# schematic.net
KiCad netlist of a schematic drawn in Altium Designer
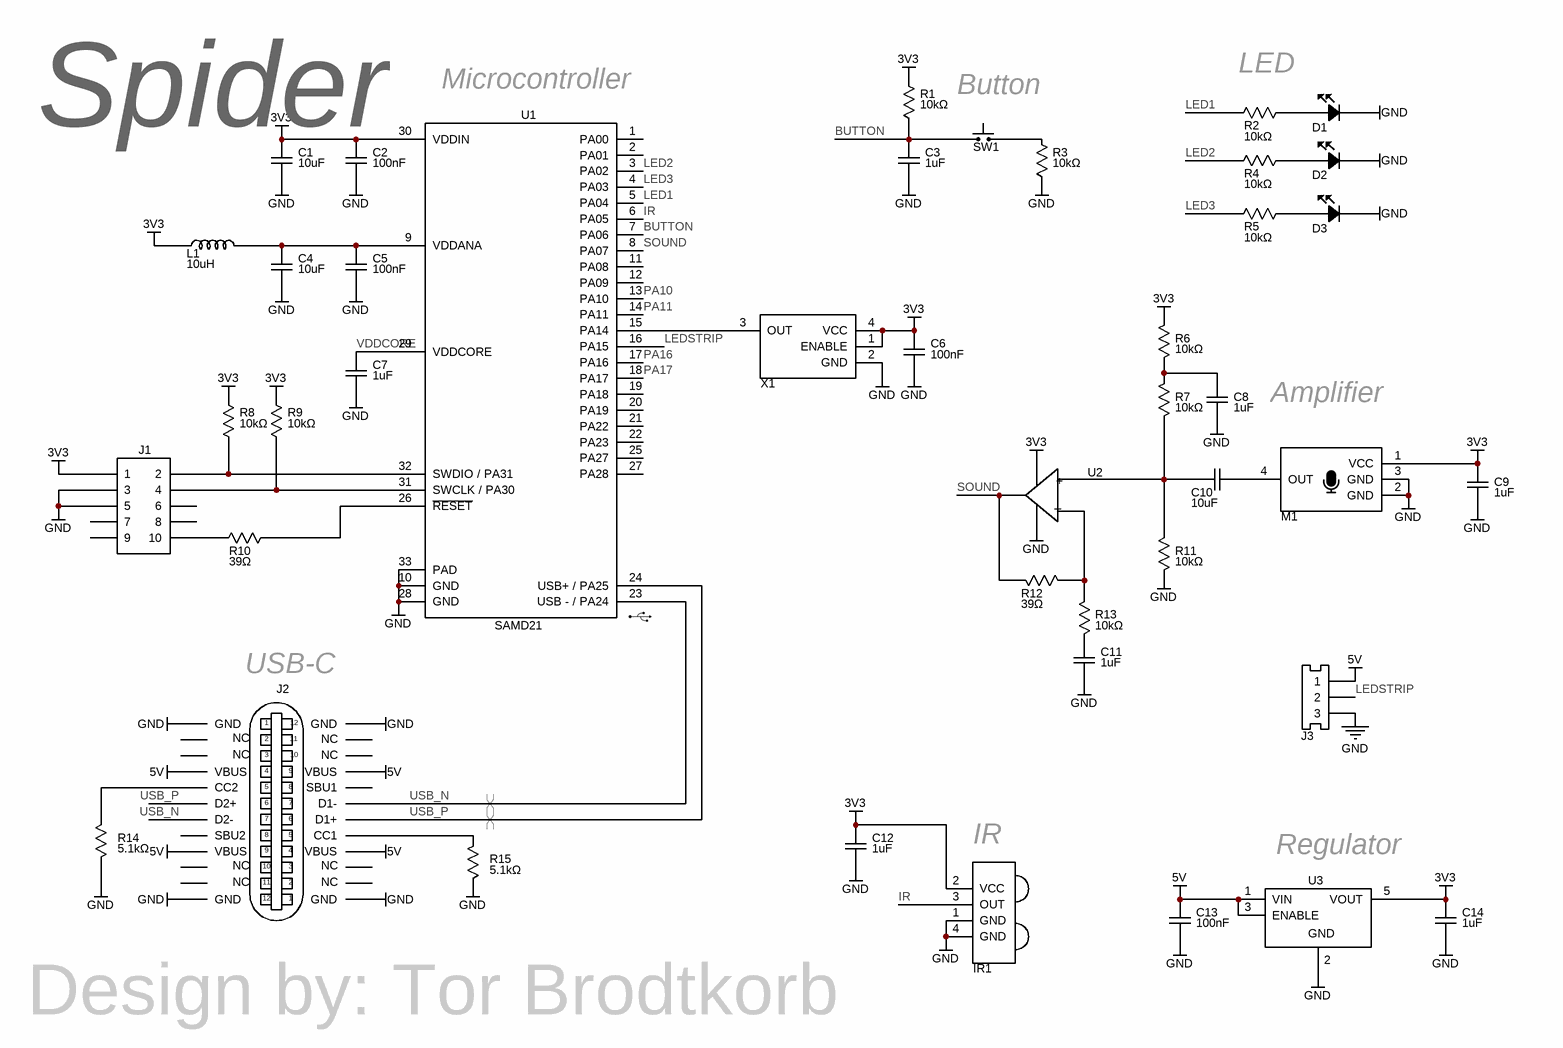
[diagram p0: schematic.SchDoc]

(export (version "E")
  (design (tool "Eeschema 10.0.6"))
  (components
    (comp (ref "C1")
      (value "10uF")
      (footprint "capacitor 0603")
      (description "Capacitor 0603")
      (fields (field (name "Comment") "passive_5"))
      (libsource (lib "passive") (part "passive_5"))
    )
    (comp (ref "C2")
      (value "100nF")
      (footprint "capacitor 0603")
      (description "Capacitor 0603")
      (fields (field (name "Comment") "passive_5"))
      (libsource (lib "passive") (part "passive_5"))
    )
    (comp (ref "C3")
      (value "1uF")
      (footprint "capacitor 0603")
      (description "Capacitor 0603")
      (fields (field (name "Comment") "passive_5"))
      (libsource (lib "passive") (part "passive_5"))
    )
    (comp (ref "C4")
      (value "10uF")
      (footprint "capacitor 0603")
      (description "Capacitor 0603")
      (fields (field (name "Comment") "passive_5"))
      (libsource (lib "passive") (part "passive_5"))
    )
    (comp (ref "C5")
      (value "100nF")
      (footprint "capacitor 0603")
      (description "Capacitor 0603")
      (fields (field (name "Comment") "passive_5"))
      (libsource (lib "passive") (part "passive_5"))
    )
    (comp (ref "C6")
      (value "100nF")
      (footprint "capacitor 0603")
      (description "Capacitor 0603")
      (fields (field (name "Comment") "passive_5"))
      (libsource (lib "passive") (part "passive_5"))
    )
    (comp (ref "C7")
      (value "1uF")
      (footprint "capacitor 0603")
      (description "Capacitor 0603")
      (fields (field (name "Comment") "passive_5"))
      (libsource (lib "passive") (part "passive_5"))
    )
    (comp (ref "C8")
      (value "1uF")
      (footprint "capacitor 0603")
      (description "Capacitor 0603")
      (fields (field (name "Comment") "passive_5"))
      (libsource (lib "passive") (part "passive_5"))
    )
    (comp (ref "C9")
      (value "1uF")
      (footprint "capacitor 0603")
      (description "Capacitor 0603")
      (fields (field (name "Comment") "passive_5"))
      (libsource (lib "passive") (part "passive_5"))
    )
    (comp (ref "C10")
      (value "10uF")
      (footprint "capacitor 0603")
      (description "Capacitor 0603")
      (fields (field (name "Comment") "passive_5"))
      (libsource (lib "passive") (part "passive_5"))
    )
    (comp (ref "C11")
      (value "1uF")
      (footprint "capacitor 0603")
      (description "Capacitor 0603")
      (fields (field (name "Comment") "passive_5"))
      (libsource (lib "passive") (part "passive_5"))
    )
    (comp (ref "C12")
      (value "1uF")
      (footprint "capacitor 0603")
      (description "Capacitor 0603")
      (fields (field (name "Comment") "passive_5"))
      (libsource (lib "passive") (part "passive_5"))
    )
    (comp (ref "C13")
      (value "100nF")
      (footprint "capacitor 0603")
      (description "Capacitor 0603")
      (fields (field (name "Comment") "passive_5"))
      (libsource (lib "passive") (part "passive_5"))
    )
    (comp (ref "C14")
      (value "1uF")
      (footprint "capacitor 0603")
      (description "Capacitor 0603")
      (fields (field (name "Comment") "passive_5"))
      (libsource (lib "passive") (part "passive_5"))
    )
    (comp (ref "D1")
      (value "LED White")
      (footprint "LED 0603 white")
      (description "LED 0603 white")
      (libsource (lib "diode") (part "diode_6"))
    )
    (comp (ref "D2")
      (value "LED White")
      (footprint "LED 0603 white")
      (description "LED 0603 white")
      (libsource (lib "diode") (part "diode_6"))
    )
    (comp (ref "D3")
      (value "LED White")
      (footprint "LED 0603 white")
      (description "LED 0603 white")
      (libsource (lib "diode") (part "diode_6"))
    )
    (comp (ref "IR1")
      (value "sensor_1")
      (footprint "TSSP77038TR")
      (description "IR receiver, 38 kHz, 40m, SMD")
      (libsource (lib "sensor") (part "sensor_1"))
    )
    (comp (ref "J1")
      (value "Header 1.27mm")
      (footprint "header male 2x5, pitch 1.27mm")
      (description "Header male 2x5, pitch 1.27mm")
      (libsource (lib "connector") (part "connector_17"))
    )
    (comp (ref "J2")
      (value "USB 2.0")
      (footprint "USB4105-GF-A")
      (description "USB-C (2.0)")
      (libsource (lib "connector") (part "connector_35"))
    )
    (comp (ref "J3")
      (value "connector_41")
      (footprint "S3B-XH-A (LF)(SN)")
      (description "JST connector 1x3, pitch 2.5mm, right angle, TH")
      (libsource (lib "connector") (part "connector_41"))
    )
    (comp (ref "L1")
      (value "10uH")
      (footprint "inductor 0603")
      (description "Inductor 0603")
      (fields (field (name "Comment") "passive_9"))
      (libsource (lib "passive") (part "passive_9"))
    )
    (comp (ref "M1")
      (value "sensor_2")
      (footprint "SPU0410HR5H-PB")
      (description "Microphone, MEMS, 100 Hz - 10 kHz, 3.3V,  SMD")
      (libsource (lib "sensor") (part "sensor_2"))
    )
    (comp (ref "R1")
      (value "10kΩ")
      (footprint "resistor 0603")
      (description "Resistor 0603")
      (fields (field (name "Comment") "passive_2"))
      (libsource (lib "passive") (part "passive_2"))
    )
    (comp (ref "R2")
      (value "10kΩ")
      (footprint "resistor 0603")
      (description "Resistor 0603")
      (fields (field (name "Comment") "passive_2"))
      (libsource (lib "passive") (part "passive_2"))
    )
    (comp (ref "R3")
      (value "10kΩ")
      (footprint "resistor 0603")
      (description "Resistor 0603")
      (fields (field (name "Comment") "passive_2"))
      (libsource (lib "passive") (part "passive_2"))
    )
    (comp (ref "R4")
      (value "10kΩ")
      (footprint "resistor 0603")
      (description "Resistor 0603")
      (fields (field (name "Comment") "passive_2"))
      (libsource (lib "passive") (part "passive_2"))
    )
    (comp (ref "R5")
      (value "10kΩ")
      (footprint "resistor 0603")
      (description "Resistor 0603")
      (fields (field (name "Comment") "passive_2"))
      (libsource (lib "passive") (part "passive_2"))
    )
    (comp (ref "R6")
      (value "10kΩ")
      (footprint "resistor 0603")
      (description "Resistor 0603")
      (fields (field (name "Comment") "passive_2"))
      (libsource (lib "passive") (part "passive_2"))
    )
    (comp (ref "R7")
      (value "10kΩ")
      (footprint "resistor 0603")
      (description "Resistor 0603")
      (fields (field (name "Comment") "passive_2"))
      (libsource (lib "passive") (part "passive_2"))
    )
    (comp (ref "R8")
      (value "10kΩ")
      (footprint "resistor 0603")
      (description "Resistor 0603")
      (fields (field (name "Comment") "passive_2"))
      (libsource (lib "passive") (part "passive_2"))
    )
    (comp (ref "R9")
      (value "10kΩ")
      (footprint "resistor 0603")
      (description "Resistor 0603")
      (fields (field (name "Comment") "passive_2"))
      (libsource (lib "passive") (part "passive_2"))
    )
    (comp (ref "R10")
      (value "39Ω")
      (footprint "resistor 0603")
      (description "Resistor 0603")
      (fields (field (name "Comment") "passive_2"))
      (libsource (lib "passive") (part "passive_2"))
    )
    (comp (ref "R11")
      (value "10kΩ")
      (footprint "resistor 0603")
      (description "Resistor 0603")
      (fields (field (name "Comment") "passive_2"))
      (libsource (lib "passive") (part "passive_2"))
    )
    (comp (ref "R12")
      (value "39Ω")
      (footprint "resistor 0603")
      (description "Resistor 0603")
      (fields (field (name "Comment") "passive_2"))
      (libsource (lib "passive") (part "passive_2"))
    )
    (comp (ref "R13")
      (value "10kΩ")
      (footprint "resistor 0603")
      (description "Resistor 0603")
      (fields (field (name "Comment") "passive_2"))
      (libsource (lib "passive") (part "passive_2"))
    )
    (comp (ref "R14")
      (value "5.1kΩ")
      (footprint "resistor 0603")
      (description "Resistor 0603")
      (fields (field (name "Comment") "passive_2"))
      (libsource (lib "passive") (part "passive_2"))
    )
    (comp (ref "R15")
      (value "5.1kΩ")
      (footprint "resistor 0603")
      (description "Resistor 0603")
      (fields (field (name "Comment") "passive_2"))
      (libsource (lib "passive") (part "passive_2"))
    )
    (comp (ref "SW1")
      (value "connector_35")
      (footprint "KMR621NG LFS")
      (description "Tactile switch SMD, tiny")
      (libsource (lib "sensor") (part "connector_35"))
    )
    (comp (ref "U1")
      (value "SAMD21")
      (footprint "ATSAMD21E17D-MUT")
      (description "SAMD21, 48 MHz, 128KB flash, 16KB RAM, 32 pins, USB device, QFN")
      (libsource (lib "cpu") (part "cpu_0"))
    )
    (comp (ref "U2")
      (value "ic_6")
      (footprint "MCP6241T-E/OT")
      (description "OpAmp, 1 circuit, rail-to-rail, single supply, 1.8V to 5V, SOT23-5")
      (libsource (lib "integrated-circuit") (part "ic_6"))
    )
    (comp (ref "U3")
      (value "regulator_1")
      (footprint "TCR2EF33,LM(CT")
      (description "LDO fixed, 3.3V output, 0.2V dropout, 200mA")
      (libsource (lib "voltage-regulator") (part "regulator_1"))
    )
    (comp (ref "X1")
      (value "8 MHz")
      (footprint "DSC6001CE2A-008.0000")
      (description "Oscillator, 8MHz, 3.3V, 3.2mm x 2.5mm")
      (libsource (lib "oscillator") (part "oscillator_2"))
    )
  )
  (nets
    (net (code "1") (name "/BUTTON") (class "Default")
      (node (ref "C3") (pin "2") (pinfunction "2_2") (pintype "passive"))
      (node (ref "R1") (pin "2") (pinfunction "2_2") (pintype "passive"))
      (node (ref "SW1") (pin "1") (pintype "passive"))
      (node (ref "U1") (pin "7") (pinfunction "PA06_7") (pintype "passive"))
    )
    (net (code "2") (name "/IR") (class "Default")
      (node (ref "IR1") (pin "3") (pinfunction "OUT_3") (pintype "passive"))
      (node (ref "U1") (pin "6") (pinfunction "PA05_6") (pintype "passive"))
    )
    (net (code "3") (name "/LED1") (class "Default")
      (node (ref "R2") (pin "2") (pinfunction "2_2") (pintype "passive"))
      (node (ref "U1") (pin "5") (pinfunction "PA04_5") (pintype "passive"))
    )
    (net (code "4") (name "/LED2") (class "Default")
      (node (ref "R4") (pin "2") (pinfunction "2_2") (pintype "passive"))
      (node (ref "U1") (pin "3") (pinfunction "PA02_3") (pintype "passive"))
    )
    (net (code "5") (name "/LED3") (class "Default")
      (node (ref "R5") (pin "2") (pinfunction "2_2") (pintype "passive"))
      (node (ref "U1") (pin "4") (pinfunction "PA03_4") (pintype "passive"))
    )
    (net (code "6") (name "/LEDSTRIP") (class "Default")
      (node (ref "J3") (pin "2") (pinfunction "2_2") (pintype "passive"))
      (node (ref "U1") (pin "16") (pinfunction "PA15_16") (pintype "passive"))
    )
    (net (code "7") (name "/PA10") (class "Default")
      (node (ref "U1") (pin "13") (pinfunction "PA10_13") (pintype "passive"))
    )
    (net (code "8") (name "/PA11") (class "Default")
      (node (ref "U1") (pin "14") (pinfunction "PA11_14") (pintype "passive"))
    )
    (net (code "9") (name "/PA16") (class "Default")
      (node (ref "U1") (pin "17") (pinfunction "PA16_17") (pintype "passive"))
    )
    (net (code "10") (name "/PA17") (class "Default")
      (node (ref "U1") (pin "18") (pinfunction "PA17_18") (pintype "passive"))
    )
    (net (code "11") (name "/SOUND") (class "Default")
      (node (ref "R12") (pin "2") (pinfunction "2_2") (pintype "passive"))
      (node (ref "U1") (pin "8") (pinfunction "PA07_8") (pintype "passive"))
      (node (ref "U2") (pin "1") (pintype "passive"))
    )
    (net (code "12") (name "/USB_N") (class "Default")
      (node (ref "J2") (pin "A7") (pinfunction "D1-_A7") (pintype "passive"))
      (node (ref "J2") (pin "B7") (pinfunction "D2-_B7") (pintype "passive"))
      (node (ref "U1") (pin "23") (pinfunction "USB_-_/_PA24_23") (pintype "passive"))
    )
    (net (code "13") (name "/USB_P") (class "Default")
      (node (ref "J2") (pin "A6") (pinfunction "D1+_A6") (pintype "passive"))
      (node (ref "J2") (pin "B6") (pinfunction "D2+_B6") (pintype "passive"))
      (node (ref "U1") (pin "24") (pinfunction "USB+_/_PA25_24") (pintype "passive"))
    )
    (net (code "14") (name "/VDDCORE") (class "Default")
      (node (ref "C7") (pin "2") (pinfunction "2_2") (pintype "passive"))
      (node (ref "U1") (pin "29") (pinfunction "VDDCORE_29") (pintype "passive"))
    )
    (net (code "15") (name "3V3") (class "Default")
      (node (ref "C1") (pin "2") (pinfunction "2_2") (pintype "passive"))
      (node (ref "C12") (pin "2") (pinfunction "2_2") (pintype "passive"))
      (node (ref "C14") (pin "2") (pinfunction "2_2") (pintype "passive"))
      (node (ref "C2") (pin "2") (pinfunction "2_2") (pintype "passive"))
      (node (ref "C6") (pin "2") (pinfunction "2_2") (pintype "passive"))
      (node (ref "C9") (pin "2") (pinfunction "2_2") (pintype "passive"))
      (node (ref "IR1") (pin "2") (pinfunction "VCC_2") (pintype "passive"))
      (node (ref "J1") (pin "1") (pinfunction "1_1") (pintype "passive"))
      (node (ref "L1") (pin "1") (pintype "passive"))
      (node (ref "M1") (pin "1") (pinfunction "VCC_1") (pintype "passive"))
      (node (ref "R1") (pin "1") (pintype "passive"))
      (node (ref "R6") (pin "2") (pinfunction "2_2") (pintype "passive"))
      (node (ref "R8") (pin "2") (pinfunction "2_2") (pintype "passive"))
      (node (ref "R9") (pin "2") (pinfunction "2_2") (pintype "passive"))
      (node (ref "U1") (pin "30") (pinfunction "VDDIN_30") (pintype "passive"))
      (node (ref "U2") (pin "5") (pintype "passive"))
      (node (ref "U3") (pin "5") (pinfunction "VOUT_5") (pintype "passive"))
      (node (ref "X1") (pin "1") (pinfunction "ENABLE_1") (pintype "passive"))
      (node (ref "X1") (pin "4") (pinfunction "VCC_4") (pintype "passive"))
    )
    (net (code "16") (name "5V") (class "Default")
      (node (ref "C13") (pin "2") (pinfunction "2_2") (pintype "passive"))
      (node (ref "J2") (pin "A4_B9") (pinfunction "VBUS_A4_B9") (pintype "passive"))
      (node (ref "J2") (pin "B4_A9") (pinfunction "VBUS_B4_A9") (pintype "passive"))
      (node (ref "J3") (pin "1") (pinfunction "1_1") (pintype "passive"))
      (node (ref "U3") (pin "1") (pinfunction "VIN_1") (pintype "passive"))
      (node (ref "U3") (pin "3") (pinfunction "ENABLE_3") (pintype "passive"))
    )
    (net (code "17") (name "GND") (class "Default")
      (node (ref "C1") (pin "1") (pinfunction "1_1") (pintype "passive"))
      (node (ref "C11") (pin "1") (pinfunction "1_1") (pintype "passive"))
      (node (ref "C12") (pin "1") (pinfunction "1_1") (pintype "passive"))
      (node (ref "C13") (pin "1") (pinfunction "1_1") (pintype "passive"))
      (node (ref "C14") (pin "1") (pinfunction "1_1") (pintype "passive"))
      (node (ref "C2") (pin "1") (pinfunction "1_1") (pintype "passive"))
      (node (ref "C3") (pin "1") (pinfunction "1_1") (pintype "passive"))
      (node (ref "C4") (pin "1") (pinfunction "1_1") (pintype "passive"))
      (node (ref "C5") (pin "1") (pinfunction "1_1") (pintype "passive"))
      (node (ref "C6") (pin "1") (pinfunction "1_1") (pintype "passive"))
      (node (ref "C7") (pin "1") (pinfunction "1_1") (pintype "passive"))
      (node (ref "C8") (pin "1") (pinfunction "1_1") (pintype "passive"))
      (node (ref "C9") (pin "1") (pinfunction "1_1") (pintype "passive"))
      (node (ref "D1") (pin "2") (pinfunction "2_2") (pintype "passive"))
      (node (ref "D2") (pin "2") (pinfunction "2_2") (pintype "passive"))
      (node (ref "D3") (pin "2") (pinfunction "2_2") (pintype "passive"))
      (node (ref "IR1") (pin "1") (pinfunction "GND_1") (pintype "passive"))
      (node (ref "IR1") (pin "4") (pinfunction "GND_4") (pintype "passive"))
      (node (ref "J1") (pin "3") (pinfunction "3_3") (pintype "passive"))
      (node (ref "J1") (pin "5") (pinfunction "5_5") (pintype "passive"))
      (node (ref "J2") (pin "A1_B12") (pinfunction "GND_A1_B12") (pintype "passive"))
      (node (ref "J2") (pin "B1_A12") (pinfunction "GND_B1_A12") (pintype "passive"))
      (node (ref "J3") (pin "3") (pinfunction "3_3") (pintype "passive"))
      (node (ref "M1") (pin "2") (pinfunction "GND_2") (pintype "passive"))
      (node (ref "M1") (pin "3") (pinfunction "GND_3") (pintype "passive"))
      (node (ref "R11") (pin "1") (pintype "passive"))
      (node (ref "R14") (pin "1") (pintype "passive"))
      (node (ref "R15") (pin "1") (pintype "passive"))
      (node (ref "R3") (pin "2") (pinfunction "2_2") (pintype "passive"))
      (node (ref "U1") (pin "10") (pinfunction "GND_10") (pintype "passive"))
      (node (ref "U1") (pin "28") (pinfunction "GND_28") (pintype "passive"))
      (node (ref "U1") (pin "33") (pinfunction "PAD_33") (pintype "passive"))
      (node (ref "U2") (pin "2") (pintype "passive"))
      (node (ref "U3") (pin "2") (pintype "passive"))
      (node (ref "X1") (pin "2") (pinfunction "GND_2") (pintype "passive"))
    )
    (net (code "18") (name "Net-(C8-Pad2)") (class "Default")
      (node (ref "C8") (pin "2") (pinfunction "2_2") (pintype "passive"))
      (node (ref "R6") (pin "1") (pintype "passive"))
      (node (ref "R7") (pin "2") (pinfunction "2_2") (pintype "passive"))
    )
    (net (code "19") (name "Net-(C10-Pad1)") (class "Default")
      (node (ref "C10") (pin "1") (pinfunction "1_1") (pintype "passive"))
      (node (ref "R11") (pin "2") (pinfunction "2_2") (pintype "passive"))
      (node (ref "R7") (pin "1") (pintype "passive"))
      (node (ref "U2") (pin "3") (pintype "passive"))
    )
    (net (code "20") (name "Net-(C11-Pad2)") (class "Default")
      (node (ref "C11") (pin "2") (pinfunction "2_2") (pintype "passive"))
      (node (ref "R13") (pin "1") (pintype "passive"))
    )
    (net (code "21") (name "Net-(D1-Pad1)") (class "Default")
      (node (ref "D1") (pin "1") (pinfunction "1_1") (pintype "passive"))
      (node (ref "R2") (pin "1") (pintype "passive"))
    )
    (net (code "22") (name "Net-(D2-Pad1)") (class "Default")
      (node (ref "D2") (pin "1") (pinfunction "1_1") (pintype "passive"))
      (node (ref "R4") (pin "1") (pintype "passive"))
    )
    (net (code "23") (name "Net-(D3-Pad1)") (class "Default")
      (node (ref "D3") (pin "1") (pinfunction "1_1") (pintype "passive"))
      (node (ref "R5") (pin "1") (pintype "passive"))
    )
    (net (code "24") (name "Net-(J1-Pad10)") (class "Default")
      (node (ref "J1") (pin "10") (pinfunction "10_10") (pintype "passive"))
      (node (ref "R10") (pin "1") (pintype "passive"))
    )
    (net (code "25") (name "Net-(J2-CC1)") (class "Default")
      (node (ref "J2") (pin "A5") (pinfunction "CC1_A5") (pintype "passive"))
      (node (ref "R15") (pin "2") (pinfunction "2_2") (pintype "passive"))
    )
    (net (code "26") (name "Net-(J2-CC2)") (class "Default")
      (node (ref "J2") (pin "B5") (pinfunction "CC2_B5") (pintype "passive"))
      (node (ref "R14") (pin "2") (pinfunction "2_2") (pintype "passive"))
    )
    (net (code "27") (name "Net-(M1-OUT)") (class "Default")
      (node (ref "C10") (pin "2") (pinfunction "2_2") (pintype "passive"))
      (node (ref "M1") (pin "4") (pinfunction "OUT_4") (pintype "passive"))
    )
    (net (code "28") (name "Net-(R3-Pad1)") (class "Default")
      (node (ref "R3") (pin "1") (pintype "passive"))
      (node (ref "SW1") (pin "2") (pintype "passive"))
    )
    (net (code "29") (name "Net-(R12-Pad1)") (class "Default")
      (node (ref "R12") (pin "1") (pintype "passive"))
      (node (ref "R13") (pin "2") (pinfunction "2_2") (pintype "passive"))
      (node (ref "U2") (pin "4") (pintype "passive"))
    )
    (net (code "30") (name "Net-(U1-PA14)") (class "Default")
      (node (ref "U1") (pin "15") (pinfunction "PA14_15") (pintype "passive"))
      (node (ref "X1") (pin "3") (pinfunction "OUT_3") (pintype "passive"))
    )
    (net (code "31") (name "Net-(U1-SWCLK_{slash}_PA30)") (class "Default")
      (node (ref "J1") (pin "4") (pinfunction "4_4") (pintype "passive"))
      (node (ref "R9") (pin "1") (pintype "passive"))
      (node (ref "U1") (pin "31") (pinfunction "SWCLK_/_PA30_31") (pintype "passive"))
    )
    (net (code "32") (name "Net-(U1-SWDIO_{slash}_PA31)") (class "Default")
      (node (ref "J1") (pin "2") (pinfunction "2_2") (pintype "passive"))
      (node (ref "R8") (pin "1") (pintype "passive"))
      (node (ref "U1") (pin "32") (pinfunction "SWDIO_/_PA31_32") (pintype "passive"))
    )
    (net (code "33") (name "Net-(U1-VDDANA)") (class "Default")
      (node (ref "C4") (pin "2") (pinfunction "2_2") (pintype "passive"))
      (node (ref "C5") (pin "2") (pinfunction "2_2") (pintype "passive"))
      (node (ref "L1") (pin "2") (pinfunction "2_2") (pintype "passive"))
      (node (ref "U1") (pin "9") (pinfunction "VDDANA_9") (pintype "passive"))
    )
    (net (code "34") (name "Net-(U1-~{RESET})") (class "Default")
      (node (ref "R10") (pin "2") (pinfunction "2_2") (pintype "passive"))
      (node (ref "U1") (pin "26") (pinfunction "~{RESET}_26") (pintype "passive"))
    )
    (net (code "35") (name "unconnected-(J1-Pad6)") (class "Default")
      (node (ref "J1") (pin "6") (pinfunction "6_6") (pintype "passive"))
    )
    (net (code "36") (name "unconnected-(J1-Pad7)") (class "Default")
      (node (ref "J1") (pin "7") (pinfunction "7_7") (pintype "passive"))
    )
    (net (code "37") (name "unconnected-(J1-Pad8)") (class "Default")
      (node (ref "J1") (pin "8") (pinfunction "8_8") (pintype "passive"))
    )
    (net (code "38") (name "unconnected-(J1-Pad9)") (class "Default")
      (node (ref "J1") (pin "9") (pinfunction "9_9") (pintype "passive"))
    )
    (net (code "39") (name "unconnected-(J2-SBU1-PadA8)") (class "Default")
      (node (ref "J2") (pin "A8") (pinfunction "SBU1_A8") (pintype "passive"))
    )
    (net (code "40") (name "unconnected-(J2-SBU2-PadB8)") (class "Default")
      (node (ref "J2") (pin "B8") (pinfunction "SBU2_B8") (pintype "passive"))
    )
    (net (code "41") (name "unconnected-(U1-PA00-Pad1)") (class "Default")
      (node (ref "U1") (pin "1") (pinfunction "PA00_1") (pintype "passive"))
    )
    (net (code "42") (name "unconnected-(U1-PA01-Pad2)") (class "Default")
      (node (ref "U1") (pin "2") (pinfunction "PA01_2") (pintype "passive"))
    )
    (net (code "43") (name "unconnected-(U1-PA08-Pad11)") (class "Default")
      (node (ref "U1") (pin "11") (pinfunction "PA08_11") (pintype "passive"))
    )
    (net (code "44") (name "unconnected-(U1-PA09-Pad12)") (class "Default")
      (node (ref "U1") (pin "12") (pinfunction "PA09_12") (pintype "passive"))
    )
    (net (code "45") (name "unconnected-(U1-PA18-Pad19)") (class "Default")
      (node (ref "U1") (pin "19") (pinfunction "PA18_19") (pintype "passive"))
    )
    (net (code "46") (name "unconnected-(U1-PA19-Pad20)") (class "Default")
      (node (ref "U1") (pin "20") (pinfunction "PA19_20") (pintype "passive"))
    )
    (net (code "47") (name "unconnected-(U1-PA22-Pad21)") (class "Default")
      (node (ref "U1") (pin "21") (pinfunction "PA22_21") (pintype "passive"))
    )
    (net (code "48") (name "unconnected-(U1-PA23-Pad22)") (class "Default")
      (node (ref "U1") (pin "22") (pinfunction "PA23_22") (pintype "passive"))
    )
    (net (code "49") (name "unconnected-(U1-PA27-Pad25)") (class "Default")
      (node (ref "U1") (pin "25") (pinfunction "PA27_25") (pintype "passive"))
    )
    (net (code "50") (name "unconnected-(U1-PA28-Pad27)") (class "Default")
      (node (ref "U1") (pin "27") (pinfunction "PA28_27") (pintype "passive"))
    )
  )
)
